# LNA.net
KiCad netlist of a schematic drawn in Altium Designer
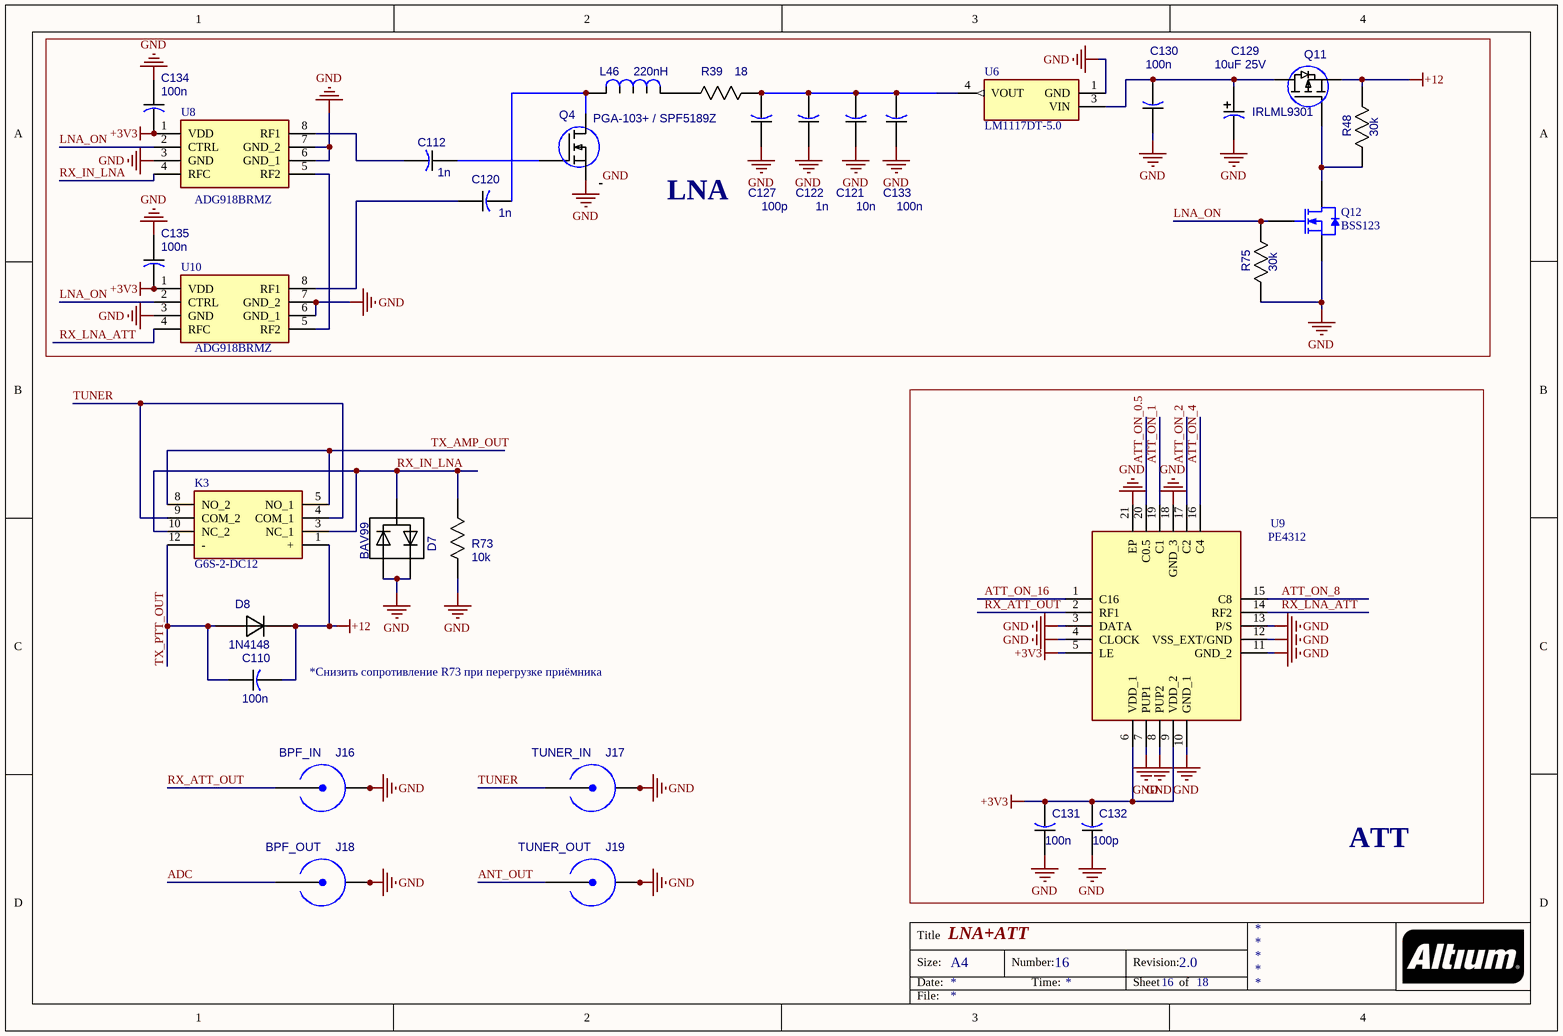
[diagram p0: LNA.SchDoc]

(export (version "E")
  (design (tool "Eeschema 10.0.6"))
  (components
    (comp (ref "C110")
      (value "100n")
      (footprint "CAP_0805")
      (description "CAP_0805")
      (libsource (lib "*") (part "CAP_0805"))
    )
    (comp (ref "C112")
      (value "1n")
      (footprint "CAP_0805")
      (description "CAP_0805")
      (libsource (lib "*") (part "CAP_0805"))
    )
    (comp (ref "C120")
      (value "1n")
      (footprint "CAP_0805")
      (description "CAP_0805")
      (libsource (lib "*") (part "CAP_0805"))
    )
    (comp (ref "C121")
      (value "10n")
      (footprint "6-0805_M")
      (description "CAP_0805")
      (libsource (lib "*") (part "CAP_0805"))
    )
    (comp (ref "C122")
      (value "1n")
      (footprint "6-0805_M")
      (description "CAP_0805")
      (libsource (lib "*") (part "CAP_0805"))
    )
    (comp (ref "C127")
      (value "100p")
      (footprint "6-0805_M")
      (description "CAP_0805")
      (libsource (lib "*") (part "CAP_0805"))
    )
    (comp (ref "C129")
      (value "10uF 25V")
      (footprint "CAPAE_5.3x5.3h6.1")
      (description "CAPAE_5.3x5.3h6.1")
      (libsource (lib "*") (part "CAPAE_5.3x5.3h6.1"))
    )
    (comp (ref "C130")
      (value "100n")
      (footprint "CAP_0805")
      (description "CAP_0805")
      (libsource (lib "") (part "CAP_0805_1"))
    )
    (comp (ref "C131")
      (value "100n")
      (footprint "6-0805_M")
      (description "CAP_0805")
      (libsource (lib "*") (part "CAP_0805"))
    )
    (comp (ref "C132")
      (value "100p")
      (footprint "6-0805_M")
      (description "CAP_0805")
      (libsource (lib "*") (part "CAP_0805"))
    )
    (comp (ref "C133")
      (value "100n")
      (footprint "CAP_0805")
      (description "CAP_0805")
      (libsource (lib "*") (part "CAP_0805"))
    )
    (comp (ref "C134")
      (value "100n")
      (footprint "CAP_0805")
      (description "CAP_0805")
      (libsource (lib "*") (part "CAP_0805"))
    )
    (comp (ref "C135")
      (value "100n")
      (footprint "CAP_0805")
      (description "CAP_0805")
      (libsource (lib "*") (part "CAP_0805"))
    )
    (comp (ref "D7") (value "BAV99") (footprint "SOT23") (libsource (lib "*") (part "BAV99")))
    (comp (ref "D8") (value "1N4148") (footprint "SS14") (libsource (lib "RF-UNIT-BIG") (part "1N4148")))
    (comp (ref "J16")
      (value "BPF_IN")
      (footprint "31-5431")
      (description "SMA")
      (libsource (lib "RF-UNIT_1") (part "31-5431"))
    )
    (comp (ref "J17")
      (value "TUNER_IN")
      (footprint "31-5431")
      (description "SMA")
      (libsource (lib "RF-UNIT_1") (part "31-5431"))
    )
    (comp (ref "J18")
      (value "BPF_OUT")
      (footprint "31-5431")
      (description "SMA")
      (libsource (lib "RF-UNIT_1") (part "31-5431"))
    )
    (comp (ref "J19")
      (value "TUNER_OUT")
      (footprint "31-5431")
      (description "SMA")
      (libsource (lib "RF-UNIT_1") (part "31-5431"))
    )
    (comp (ref "K3")
      (value "G6S-2-DC12")
      (footprint "G6S2DC12")
      (description "Relay or Contactor")
      (fields (field (name "MOUSER PART NUMBER") "653-G6S-2-DC12A"))
      (libsource (lib "*") (part "G6S-2-DC12"))
    )
    (comp (ref "L46")
      (value "220nH")
      (footprint "IND_1206")
      (description "IND_1206")
      (libsource (lib "*") (part "IND_1206"))
    )
    (comp (ref "Q4")
      (value "PGA-103+ / SPF5189Z")
      (footprint "SOT89")
      (libsource (lib "*") (part "PGA-103+"))
    )
    (comp (ref "Q11")
      (value "IRLML9301")
      (footprint "SOT23")
      (description "MOSFET")
      (libsource (lib "*") (part "MOSFET_ENH_PD"))
    )
    (comp (ref "Q12")
      (value "BSS123")
      (footprint "FAIR-SOT23-3_V")
      (fields (field (name "MANUFACTURER") "Fairchild"))
      (libsource (lib "Altium Content Vault") (part "NEMOS-GSD-3"))
    )
    (comp (ref "R39")
      (value "18")
      (footprint "RES_1206")
      (description "RES_1206")
      (libsource (lib "*") (part "RES_1206"))
    )
    (comp (ref "R48")
      (value "30k")
      (footprint "RES_0805")
      (description "RES_0805")
      (libsource (lib "*") (part "RES_0805"))
    )
    (comp (ref "R73")
      (value "10k")
      (footprint "RES_1206")
      (description "RES_1206")
      (libsource (lib "*") (part "RES_1206"))
    )
    (comp (ref "R75")
      (value "30k")
      (footprint "RES_0805")
      (description "RES_0805")
      (libsource (lib "*") (part "RES_0805"))
    )
    (comp (ref "U6")
      (value "LM1117DT-5.0")
      (footprint "SamacSys:TO228P991X238-3N")
      (description "Integrated Circuit")
      (fields
        (field (name "MANUFACTURER_PART_NUMBER") "LM1117DT-ADJ")
        (field (name "MOUSER PART NUMBER") "926-LM1117DT-ADJ")
      )
      (libsource (lib "*") (part "LM1117DT-ADJ"))
    )
    (comp (ref "U8")
      (value "ADG918BRMZ")
      (footprint "SOP65P490X110-8N")
      (description "Integrated Circuit")
      (fields (field (name "MOUSER PART NUMBER") "584-ADG918BRMZ") (field (name "RS PART NUMBER") "4969212P"))
      (libsource (lib "RF-UNIT-BIG") (part "ADG918BRMZ"))
    )
    (comp (ref "U9")
      (value "PE4312")
      (footprint "QFN50P400X400X90-21N")
      (description "Integrated Circuit")
      (fields (field (name "MANUFACTURER_PART_NUMBER") "PE4312C-Z"))
      (libsource (lib "RF-UNIT-BIG") (part "PE4312C-Z"))
    )
    (comp (ref "U10")
      (value "ADG918BRMZ")
      (footprint "SOP65P490X110-8N")
      (description "Integrated Circuit")
      (fields (field (name "MOUSER PART NUMBER") "584-ADG918BRMZ") (field (name "RS PART NUMBER") "4969212P"))
      (libsource (lib "RF-UNIT-BIG") (part "ADG918BRMZ"))
    )
  )
  (nets
    (net (code "1") (name "+3V3") (class "Default")
      (node (ref "C131") (pin "2") (pinfunction "2_2") (pintype "passive"))
      (node (ref "C132") (pin "2") (pinfunction "2_2") (pintype "passive"))
      (node (ref "C134") (pin "2") (pinfunction "2_2") (pintype "passive"))
      (node (ref "C135") (pin "2") (pinfunction "2_2") (pintype "passive"))
      (node (ref "U10") (pin "1") (pinfunction "VDD_1") (pintype "power_in"))
      (node (ref "U8") (pin "1") (pinfunction "VDD_1") (pintype "power_in"))
      (node (ref "U9") (pin "5") (pinfunction "LE_5") (pintype "passive"))
      (node (ref "U9") (pin "6") (pinfunction "VDD_1_6") (pintype "passive"))
      (node (ref "U9") (pin "9") (pinfunction "VDD_2_9") (pintype "passive"))
    )
    (net (code "2") (name "+12") (class "Default")
      (node (ref "C110") (pin "2") (pinfunction "2_2") (pintype "passive"))
      (node (ref "D8") (pin "1") (pinfunction "K_1") (pintype "passive"))
      (node (ref "K3") (pin "1") (pinfunction "+_1") (pintype "passive"))
      (node (ref "Q11") (pin "2") (pinfunction "S_2") (pintype "passive"))
      (node (ref "R48") (pin "2") (pinfunction "2_2") (pintype "passive"))
    )
    (net (code "3") (name "/ADC") (class "Default")
      (node (ref "J18") (pin "5") (pinfunction "CON_5") (pintype "passive"))
    )
    (net (code "4") (name "/ANT_OUT") (class "Default")
      (node (ref "J19") (pin "5") (pinfunction "CON_5") (pintype "passive"))
    )
    (net (code "5") (name "/ATT_ON_0.5") (class "Default")
      (node (ref "U9") (pin "20") (pinfunction "C0.5_20") (pintype "passive"))
    )
    (net (code "6") (name "/ATT_ON_1") (class "Default")
      (node (ref "U9") (pin "19") (pinfunction "C1_19") (pintype "passive"))
    )
    (net (code "7") (name "/ATT_ON_2") (class "Default")
      (node (ref "U9") (pin "17") (pinfunction "C2_17") (pintype "passive"))
    )
    (net (code "8") (name "/ATT_ON_4") (class "Default")
      (node (ref "U9") (pin "16") (pinfunction "C4_16") (pintype "passive"))
    )
    (net (code "9") (name "/ATT_ON_8") (class "Default")
      (node (ref "U9") (pin "15") (pinfunction "C8_15") (pintype "passive"))
    )
    (net (code "10") (name "/ATT_ON_16") (class "Default")
      (node (ref "U9") (pin "1") (pinfunction "C16_1") (pintype "passive"))
    )
    (net (code "11") (name "/LNA_ON") (class "Default")
      (node (ref "Q12") (pin "1") (pinfunction "G_1") (pintype "passive"))
      (node (ref "R75") (pin "2") (pinfunction "2_2") (pintype "passive"))
      (node (ref "U10") (pin "2") (pinfunction "CTRL_2") (pintype "passive"))
      (node (ref "U8") (pin "2") (pinfunction "CTRL_2") (pintype "passive"))
    )
    (net (code "12") (name "/RX_ATT_OUT") (class "Default")
      (node (ref "J16") (pin "5") (pinfunction "CON_5") (pintype "passive"))
      (node (ref "U9") (pin "2") (pinfunction "RF1_2") (pintype "passive"))
    )
    (net (code "13") (name "/RX_IN_LNA") (class "Default")
      (node (ref "D7") (pin "3") (pinfunction "C(D1),A(D2)_3") (pintype "passive"))
      (node (ref "K3") (pin "10") (pinfunction "NC_2_10") (pintype "passive"))
      (node (ref "K3") (pin "3") (pinfunction "NC_1_3") (pintype "passive"))
      (node (ref "R73") (pin "2") (pinfunction "2_2") (pintype "passive"))
      (node (ref "U8") (pin "4") (pinfunction "RFC_4") (pintype "passive"))
    )
    (net (code "14") (name "/RX_LNA_ATT") (class "Default")
      (node (ref "U10") (pin "4") (pinfunction "RFC_4") (pintype "passive"))
      (node (ref "U9") (pin "14") (pinfunction "RF2_14") (pintype "passive"))
    )
    (net (code "15") (name "/TUNER") (class "Default")
      (node (ref "J17") (pin "5") (pinfunction "CON_5") (pintype "passive"))
      (node (ref "K3") (pin "4") (pinfunction "COM_1_4") (pintype "passive"))
      (node (ref "K3") (pin "9") (pinfunction "COM_2_9") (pintype "passive"))
    )
    (net (code "16") (name "/TX_AMP_OUT") (class "Default")
      (node (ref "K3") (pin "5") (pinfunction "NO_1_5") (pintype "passive"))
      (node (ref "K3") (pin "8") (pinfunction "NO_2_8") (pintype "passive"))
    )
    (net (code "17") (name "/TX_PTT_OUT") (class "Default")
      (node (ref "C110") (pin "1") (pinfunction "1_1") (pintype "passive"))
      (node (ref "D8") (pin "2") (pinfunction "A_2") (pintype "passive"))
      (node (ref "K3") (pin "12") (pinfunction "-_12") (pintype "passive"))
    )
    (net (code "18") (name "GND") (class "Default")
      (node (ref "C121") (pin "1") (pinfunction "1_1") (pintype "passive"))
      (node (ref "C122") (pin "1") (pinfunction "1_1") (pintype "passive"))
      (node (ref "C127") (pin "1") (pinfunction "1_1") (pintype "passive"))
      (node (ref "C129") (pin "2") (pinfunction "MINUS_2") (pintype "passive"))
      (node (ref "C130") (pin "1") (pinfunction "1_1") (pintype "passive"))
      (node (ref "C131") (pin "1") (pinfunction "1_1") (pintype "passive"))
      (node (ref "C132") (pin "1") (pinfunction "1_1") (pintype "passive"))
      (node (ref "C133") (pin "1") (pinfunction "1_1") (pintype "passive"))
      (node (ref "C134") (pin "1") (pinfunction "1_1") (pintype "passive"))
      (node (ref "C135") (pin "1") (pinfunction "1_1") (pintype "passive"))
      (node (ref "D7") (pin "1") (pinfunction "A(D1)_1") (pintype "passive"))
      (node (ref "D7") (pin "2") (pinfunction "C(D2)_2") (pintype "passive"))
      (node (ref "J16") (pin "1") (pinfunction "GND_1") (pintype "passive"))
      (node (ref "J16") (pin "2") (pinfunction "GND_2") (pintype "passive"))
      (node (ref "J16") (pin "3") (pinfunction "GND_3") (pintype "passive"))
      (node (ref "J16") (pin "4") (pinfunction "GND_4") (pintype "passive"))
      (node (ref "J17") (pin "1") (pinfunction "GND_1") (pintype "passive"))
      (node (ref "J17") (pin "2") (pinfunction "GND_2") (pintype "passive"))
      (node (ref "J17") (pin "3") (pinfunction "GND_3") (pintype "passive"))
      (node (ref "J17") (pin "4") (pinfunction "GND_4") (pintype "passive"))
      (node (ref "J18") (pin "1") (pinfunction "GND_1") (pintype "passive"))
      (node (ref "J18") (pin "2") (pinfunction "GND_2") (pintype "passive"))
      (node (ref "J18") (pin "3") (pinfunction "GND_3") (pintype "passive"))
      (node (ref "J18") (pin "4") (pinfunction "GND_4") (pintype "passive"))
      (node (ref "J19") (pin "1") (pinfunction "GND_1") (pintype "passive"))
      (node (ref "J19") (pin "2") (pinfunction "GND_2") (pintype "passive"))
      (node (ref "J19") (pin "3") (pinfunction "GND_3") (pintype "passive"))
      (node (ref "J19") (pin "4") (pinfunction "GND_4") (pintype "passive"))
      (node (ref "Q12") (pin "2") (pinfunction "S_2") (pintype "passive"))
      (node (ref "Q4") (pin "0") (pinfunction "0_0") (pintype "passive"))
      (node (ref "Q4") (pin "2") (pinfunction "S_2") (pintype "passive"))
      (node (ref "R73") (pin "1") (pinfunction "1_1") (pintype "passive"))
      (node (ref "R75") (pin "1") (pinfunction "1_1") (pintype "passive"))
      (node (ref "U10") (pin "3") (pinfunction "GND_3") (pintype "power_in"))
      (node (ref "U10") (pin "6") (pinfunction "GND_1_6") (pintype "power_in"))
      (node (ref "U10") (pin "7") (pinfunction "GND_2_7") (pintype "power_in"))
      (node (ref "U6") (pin "1") (pinfunction "GND_1") (pintype "passive"))
      (node (ref "U8") (pin "3") (pinfunction "GND_3") (pintype "power_in"))
      (node (ref "U8") (pin "6") (pinfunction "GND_1_6") (pintype "power_in"))
      (node (ref "U8") (pin "7") (pinfunction "GND_2_7") (pintype "power_in"))
      (node (ref "U9") (pin "10") (pinfunction "GND_1_10") (pintype "passive"))
      (node (ref "U9") (pin "11") (pinfunction "GND_2_11") (pintype "passive"))
      (node (ref "U9") (pin "12") (pinfunction "VSS_EXT/GND_12") (pintype "passive"))
      (node (ref "U9") (pin "13") (pinfunction "P/S_13") (pintype "passive"))
      (node (ref "U9") (pin "18") (pinfunction "GND_3_18") (pintype "passive"))
      (node (ref "U9") (pin "21") (pinfunction "EP_21") (pintype "passive"))
      (node (ref "U9") (pin "3") (pinfunction "DATA_3") (pintype "passive"))
      (node (ref "U9") (pin "4") (pinfunction "CLOCK_4") (pintype "passive"))
      (node (ref "U9") (pin "7") (pinfunction "PUP1_7") (pintype "passive"))
      (node (ref "U9") (pin "8") (pinfunction "PUP2_8") (pintype "passive"))
    )
    (net (code "19") (name "Net-(C129-PLUS)") (class "Default")
      (node (ref "C129") (pin "1") (pinfunction "PLUS_1") (pintype "passive"))
      (node (ref "C130") (pin "2") (pinfunction "2_2") (pintype "passive"))
      (node (ref "Q11") (pin "3") (pinfunction "D_3") (pintype "passive"))
      (node (ref "U6") (pin "3") (pinfunction "VIN_3") (pintype "passive"))
    )
    (net (code "20") (name "Net-(L46-1)") (class "Default")
      (node (ref "C120") (pin "2") (pinfunction "2_2") (pintype "passive"))
      (node (ref "L46") (pin "2") (pinfunction "1_2") (pintype "passive"))
      (node (ref "Q4") (pin "3") (pinfunction "D_3") (pintype "passive"))
    )
    (net (code "21") (name "Net-(L46-2)") (class "Default")
      (node (ref "L46") (pin "1") (pinfunction "2_1") (pintype "passive"))
      (node (ref "R39") (pin "2") (pinfunction "2_2") (pintype "passive"))
    )
    (net (code "22") (name "Net-(Q4-G)") (class "Default")
      (node (ref "C112") (pin "1") (pinfunction "1_1") (pintype "passive"))
      (node (ref "Q4") (pin "1") (pinfunction "G_1") (pintype "passive"))
    )
    (net (code "23") (name "Net-(Q11-G)") (class "Default")
      (node (ref "Q11") (pin "1") (pinfunction "G_1") (pintype "passive"))
      (node (ref "Q12") (pin "3") (pinfunction "D_3") (pintype "passive"))
      (node (ref "R48") (pin "1") (pinfunction "1_1") (pintype "passive"))
    )
    (net (code "24") (name "Net-(U6-VOUT)") (class "Default")
      (node (ref "C121") (pin "2") (pinfunction "2_2") (pintype "passive"))
      (node (ref "C122") (pin "2") (pinfunction "2_2") (pintype "passive"))
      (node (ref "C127") (pin "2") (pinfunction "2_2") (pintype "passive"))
      (node (ref "C133") (pin "2") (pinfunction "2_2") (pintype "passive"))
      (node (ref "R39") (pin "1") (pinfunction "1_1") (pintype "passive"))
      (node (ref "U6") (pin "4") (pinfunction "VOUT_4") (pintype "output"))
    )
    (net (code "25") (name "Net-(U8-RF1)") (class "Default")
      (node (ref "C112") (pin "2") (pinfunction "2_2") (pintype "passive"))
      (node (ref "U8") (pin "8") (pinfunction "RF1_8") (pintype "passive"))
    )
    (net (code "26") (name "Net-(U10-RF1)") (class "Default")
      (node (ref "C120") (pin "1") (pinfunction "1_1") (pintype "passive"))
      (node (ref "U10") (pin "8") (pinfunction "RF1_8") (pintype "passive"))
    )
    (net (code "27") (name "Net-(U10-RF2)") (class "Default")
      (node (ref "U10") (pin "5") (pinfunction "RF2_5") (pintype "passive"))
      (node (ref "U8") (pin "5") (pinfunction "RF2_5") (pintype "passive"))
    )
  )
)
